# buck-converter-altium.net
KiCad netlist of a schematic drawn in Altium Designer
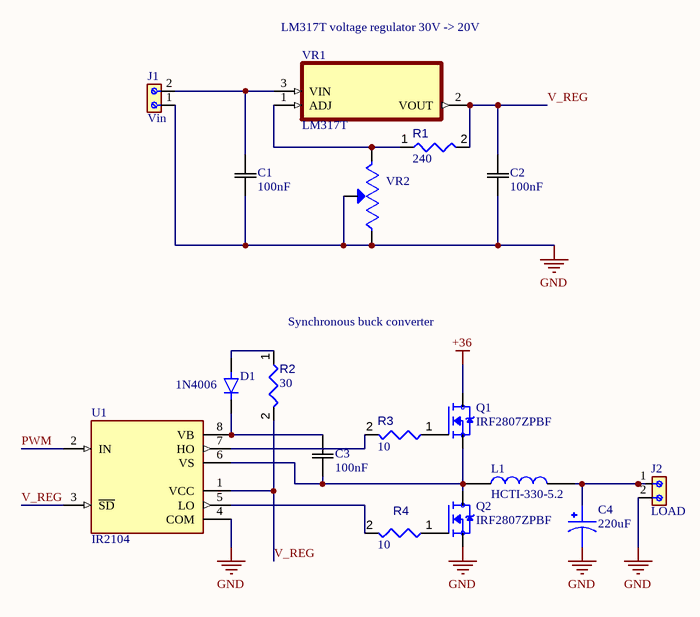
[diagram p0: buck-converter-altium.SchDoc]

(export (version "E")
  (design (tool "Eeschema 10.0.6"))
  (components
    (comp (ref "C1")
      (value "100nF")
      (footprint "CAP_R82E-7P4X2P6-5P0_KEM")
      (fields
        (field (name "MANUFACTURER_PART_NUMBER") "R82EC3100Z370J")
        (field (name "COPYRIGHT") "Copyright (C) 2026 Ultra Librarian. All rights reserved.")
      )
      (libsource (lib "R82EC3100Z370J") (part "R82EC3100Z370J"))
    )
    (comp (ref "C2")
      (value "100nF")
      (footprint "CAP_R82E-7P4X2P6-5P0_KEM")
      (fields
        (field (name "MANUFACTURER_PART_NUMBER") "R82EC3100Z370J")
        (field (name "COPYRIGHT") "Copyright (C) 2026 Ultra Librarian. All rights reserved.")
      )
      (libsource (lib "R82EC3100Z370J") (part "R82EC3100Z370J"))
    )
    (comp (ref "C3")
      (value "100nF")
      (footprint "CAP_R82E-7P4X2P6-5P0_KEM")
      (fields
        (field (name "MANUFACTURER_PART_NUMBER") "R82EC3100Z370J")
        (field (name "COPYRIGHT") "Copyright (C) 2026 Ultra Librarian. All rights reserved.")
      )
      (libsource (lib "R82EC3100Z370J") (part "R82EC3100Z370J"))
    )
    (comp (ref "C4")
      (value "220uF")
      (footprint "CAPPRD500W60D1000H1350")
      (description "220 ÂµF 35 V Aluminum Electrolytic Capacitors Radial, Can 373mOhm @ 100kHz 3000 Hrs @ 125Â°C")
      (fields (field (name "MF") "EPCOS - TDK Electronics") (field (name "MP") "B41866C7227M000"))
      (libsource (lib "B41866C7227M000") (part "B41866C7227M000"))
    )
    (comp (ref "D1")
      (value "1N4006")
      (footprint "DIOAD1036W78L470D235")
      (description "1A, 800V, Standard Rectifier")
      (fields (field (name "MF") "Taiwan Semiconductor") (field (name "MP") "1N4006GH"))
      (libsource (lib "1N4006GH") (part "1N4006GH"))
    )
    (comp (ref "J1")
      (value "Vin")
      (footprint "691103110002")
      (fields (field (name "MF") "{'manufacturer': u'Wurth Electronics'}") (field (name "MP") "691103110002"))
      (libsource (lib "691103110002") (part "691103110002"))
    )
    (comp (ref "J2")
      (value "LOAD")
      (footprint "691103110002")
      (fields (field (name "MF") "{'manufacturer': u'Wurth Electronics'}") (field (name "MP") "691103110002"))
      (libsource (lib "") (part "691103110002_1"))
    )
    (comp (ref "L1")
      (value "HCTI-330-5.2")
      (footprint "IND_HCTI-220-5.8")
      (description "High Current Toroidal Inductor ¦ 330 uH")
      (fields (field (name "MF") "Signal Transformer"))
      (libsource (lib "HCTI-330-5.2") (part "HCTI-330-5.2"))
    )
    (comp (ref "Q1")
      (value "IRF2807ZPBF")
      (footprint "TO254P1016X419X2057-3")
      (fields (field (name "MF") "Infineon"))
      (libsource (lib "IRF2807ZPBF") (part "IRF2807ZPBF"))
    )
    (comp (ref "Q2")
      (value "IRF2807ZPBF")
      (footprint "TO254P1016X419X2057-3")
      (fields (field (name "MF") "Infineon"))
      (libsource (lib "IRF2807ZPBF") (part "IRF2807ZPBF"))
    )
    (comp (ref "R1")
      (value "240")
      (footprint "RESA60-630X240")
      (description "Axial Resistor, 4.7 KOhm")
      (fields (field (name "TOLERANCE") "1%") (field (name "Comment") "4k7 resistor Axial"))
      (libsource (lib "PCB_Kursus_Library") (part "CMP-009-00178-1"))
    )
    (comp (ref "R2")
      (value "30")
      (footprint "RESA60-630X240")
      (description "Axial Resistor, 4.7 KOhm")
      (fields (field (name "TOLERANCE") "1%") (field (name "Comment") "4k7 resistor Axial"))
      (libsource (lib "PCB_Kursus_Library") (part "CMP-009-00178-1"))
    )
    (comp (ref "R3")
      (value "10")
      (footprint "RESA60-630X240")
      (description "Axial Resistor, 4.7 KOhm")
      (fields (field (name "TOLERANCE") "1%") (field (name "Comment") "4k7 resistor Axial"))
      (libsource (lib "PCB_Kursus_Library") (part "CMP-009-00178-1"))
    )
    (comp (ref "R4")
      (value "10")
      (footprint "RESA60-630X240")
      (description "Axial Resistor, 4.7 KOhm")
      (fields (field (name "TOLERANCE") "1%") (field (name "Comment") "4k7 resistor Axial"))
      (libsource (lib "PCB_Kursus_Library") (part "CMP-009-00178-1"))
    )
    (comp (ref "U1")
      (value "IR2104")
      (footprint "DIP762W45P254L988H533Q8")
      (description "Half-Bridge Gate Driver IC Non-Inverting 8-PDIP")
      (fields (field (name "MF") "Infineon Technologies"))
      (libsource (lib "IR2104") (part "IR2104"))
    )
    (comp (ref "VR1")
      (value "LM317T")
      (footprint "TO254P1054X470X1955-3")
      (description "Linear Voltage Regulator IC Positive Adjustable 1 Output 1.5A TO-220AB")
      (fields (field (name "MF") "onsemi"))
      (libsource (lib "LM317T") (part "LM317T"))
    )
    (comp (ref "VR2")
      (value "~")
      (footprint "TRIM_3296W-1-202RLF")
      (description "TRIMMER - 3/8in SQ MT CERMET ¦ Bourns 3296W-1-202RLF")
      (fields (field (name "MF") "Bourns") (field (name "MP") "3296W-1-202RLF"))
      (libsource (lib "3296W-1-202RLF") (part "3296W-1-202RLF"))
    )
  )
  (nets
    (net (code "1") (name "+36") (class "Default")
      (node (ref "Q1") (pin "2") (pinfunction "D_2") (pintype "passive"))
    )
    (net (code "2") (name "/PWM") (class "Default")
      (node (ref "U1") (pin "2") (pinfunction "IN_2") (pintype "input"))
    )
    (net (code "3") (name "/V_REG") (class "Default")
      (node (ref "C2") (pin "1") (pinfunction "1_1") (pintype "passive"))
      (node (ref "R1") (pin "2") (pinfunction "2_2") (pintype "passive"))
      (node (ref "R2") (pin "2") (pinfunction "2_2") (pintype "passive"))
      (node (ref "U1") (pin "1") (pinfunction "VCC_1") (pintype "power_in"))
      (node (ref "U1") (pin "3") (pinfunction "~{SD}_3") (pintype "input"))
      (node (ref "VR1") (pin "2") (pinfunction "VOUT_2") (pintype "output"))
    )
    (net (code "4") (name "GND") (class "Default")
      (node (ref "C1") (pin "2") (pinfunction "2_2") (pintype "passive"))
      (node (ref "C2") (pin "2") (pinfunction "2_2") (pintype "passive"))
      (node (ref "C4") (pin "2") (pinfunction "2_2") (pintype "passive"))
      (node (ref "J1") (pin "1") (pinfunction "1_1") (pintype "passive"))
      (node (ref "J2") (pin "2") (pinfunction "2_2") (pintype "passive"))
      (node (ref "Q2") (pin "3") (pinfunction "S_3") (pintype "passive"))
      (node (ref "U1") (pin "4") (pinfunction "COM_4") (pintype "power_in"))
      (node (ref "VR2") (pin "1") (pinfunction "CCW_1") (pintype "passive"))
      (node (ref "VR2") (pin "2") (pinfunction "WIPER_2") (pintype "passive"))
    )
    (net (code "5") (name "Net-(C4-Pad1)") (class "Default")
      (node (ref "C4") (pin "1") (pinfunction "1_1") (pintype "passive"))
      (node (ref "J2") (pin "1") (pinfunction "1_1") (pintype "passive"))
      (node (ref "L1") (pin "2") (pinfunction "2_2") (pintype "passive"))
    )
    (net (code "6") (name "Net-(D1-K)") (class "Default")
      (node (ref "C3") (pin "1") (pinfunction "1_1") (pintype "passive"))
      (node (ref "D1") (pin "C") (pinfunction "K_C") (pintype "passive"))
      (node (ref "U1") (pin "8") (pinfunction "VB_8") (pintype "power_in"))
    )
    (net (code "7") (name "Net-(D1-PadA)") (class "Default")
      (node (ref "D1") (pin "A") (pinfunction "A_A") (pintype "passive"))
      (node (ref "R2") (pin "1") (pinfunction "1_1") (pintype "passive"))
    )
    (net (code "8") (name "Net-(Q1-G)") (class "Default")
      (node (ref "Q1") (pin "1") (pinfunction "G_1") (pintype "passive"))
      (node (ref "R3") (pin "1") (pinfunction "1_1") (pintype "passive"))
    )
    (net (code "9") (name "Net-(Q1-S)") (class "Default")
      (node (ref "C3") (pin "2") (pinfunction "2_2") (pintype "passive"))
      (node (ref "L1") (pin "1") (pinfunction "1_1") (pintype "passive"))
      (node (ref "Q1") (pin "3") (pinfunction "S_3") (pintype "passive"))
      (node (ref "Q2") (pin "2") (pinfunction "D_2") (pintype "passive"))
      (node (ref "U1") (pin "6") (pinfunction "VS_6") (pintype "power_in"))
    )
    (net (code "10") (name "Net-(Q2-G)") (class "Default")
      (node (ref "Q2") (pin "1") (pinfunction "G_1") (pintype "passive"))
      (node (ref "R4") (pin "1") (pinfunction "1_1") (pintype "passive"))
    )
    (net (code "11") (name "Net-(U1-HO)") (class "Default")
      (node (ref "R3") (pin "2") (pinfunction "2_2") (pintype "passive"))
      (node (ref "U1") (pin "7") (pinfunction "HO_7") (pintype "output"))
    )
    (net (code "12") (name "Net-(U1-LO)") (class "Default")
      (node (ref "R4") (pin "2") (pinfunction "2_2") (pintype "passive"))
      (node (ref "U1") (pin "5") (pinfunction "LO_5") (pintype "output"))
    )
    (net (code "13") (name "Net-(VR1-ADJ)") (class "Default")
      (node (ref "R1") (pin "1") (pinfunction "1_1") (pintype "passive"))
      (node (ref "VR1") (pin "1") (pinfunction "ADJ_1") (pintype "input"))
      (node (ref "VR2") (pin "3") (pinfunction "CW_3") (pintype "passive"))
    )
    (net (code "14") (name "Net-(VR1-VIN)") (class "Default")
      (node (ref "C1") (pin "1") (pinfunction "1_1") (pintype "passive"))
      (node (ref "J1") (pin "2") (pinfunction "2_2") (pintype "passive"))
      (node (ref "VR1") (pin "3") (pinfunction "VIN_3") (pintype "input"))
    )
  )
)
